# block_demux_pwm.net
KiCad netlist of a schematic drawn in EAGLE
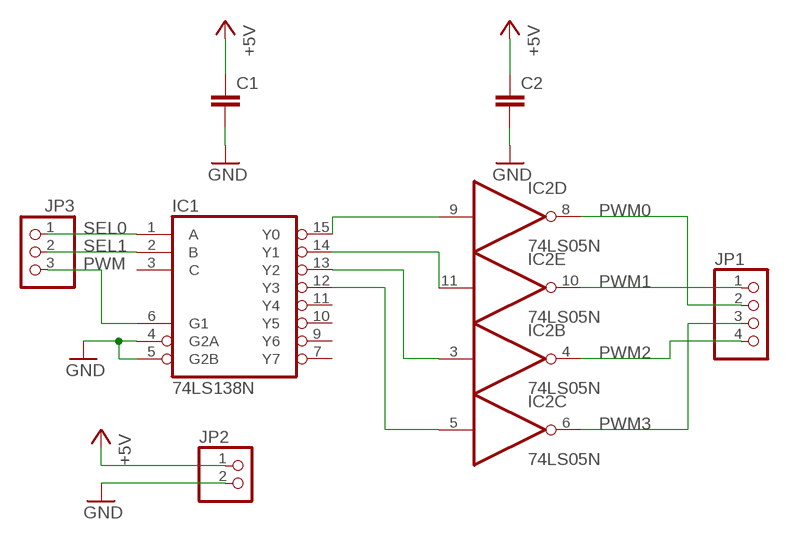
[diagram p0: schematic, sheet 1]

(export (version "E")
  (design (tool "Eeschema 10.0.6"))
  (components
    (comp (ref "C1")
      (value "C-EU050-025X075")
      (footprint "eagle-import:C050-025X075")
      (libsource (lib "eagle-import") (part "C-EU050-025X075"))
    )
    (comp (ref "C2")
      (value "C-EU050-025X075")
      (footprint "eagle-import:C050-025X075")
      (libsource (lib "eagle-import") (part "C-EU050-025X075"))
    )
    (comp (ref "IC1")
      (value "74LS138N")
      (footprint "eagle-import:DIL16")
      (libsource (lib "eagle-import") (part "74138NLS"))
    )
    (comp (ref "IC2")
      (value "74LS05N")
      (footprint "eagle-import:DIL14")
      (libsource (lib "eagle-import") (part "7405NLS"))
    )
    (comp (ref "JP1")
      (value "PINHD-1X4")
      (footprint "eagle-import:1X04")
      (libsource (lib "eagle-import") (part "PINHD-1X4"))
    )
    (comp (ref "JP2")
      (value "PINHD-1X2")
      (footprint "eagle-import:1X02")
      (libsource (lib "eagle-import") (part "PINHD-1X2"))
    )
    (comp (ref "JP3")
      (value "PINHD-1X3")
      (footprint "eagle-import:1X03")
      (libsource (lib "eagle-import") (part "PINHD-1X3"))
    )
  )
  (nets
    (net (code "1") (name "+5V") (class "Default")
      (node (ref "C1") (pin "1") (pinfunction "1_1") (pintype "passive"))
      (node (ref "C2") (pin "1") (pinfunction "1_1") (pintype "passive"))
      (node (ref "JP2") (pin "1") (pinfunction "1_1") (pintype "passive"))
    )
    (net (code "2") (name "/PWM") (class "Default")
      (node (ref "IC1") (pin "6") (pinfunction "G1_6") (pintype "input"))
      (node (ref "JP3") (pin "3") (pinfunction "3_3") (pintype "passive"))
    )
    (net (code "3") (name "/PWM0") (class "Default")
      (node (ref "IC2") (pin "8") (pinfunction "O_8") (pintype "open_collector"))
      (node (ref "JP1") (pin "2") (pinfunction "2_2") (pintype "passive"))
    )
    (net (code "4") (name "/PWM1") (class "Default")
      (node (ref "IC2") (pin "10") (pinfunction "O_10") (pintype "open_collector"))
      (node (ref "JP1") (pin "1") (pinfunction "1_1") (pintype "passive"))
    )
    (net (code "5") (name "/PWM2") (class "Default")
      (node (ref "IC2") (pin "4") (pinfunction "O_4") (pintype "open_collector"))
      (node (ref "JP1") (pin "4") (pinfunction "4_4") (pintype "passive"))
    )
    (net (code "6") (name "/PWM3") (class "Default")
      (node (ref "IC2") (pin "6") (pinfunction "O_6") (pintype "open_collector"))
      (node (ref "JP1") (pin "3") (pinfunction "3_3") (pintype "passive"))
    )
    (net (code "7") (name "/SEL0") (class "Default")
      (node (ref "IC1") (pin "1") (pinfunction "A_1") (pintype "input"))
      (node (ref "JP3") (pin "1") (pinfunction "1_1") (pintype "passive"))
    )
    (net (code "8") (name "/SEL1") (class "Default")
      (node (ref "IC1") (pin "2") (pinfunction "B_2") (pintype "input"))
      (node (ref "JP3") (pin "2") (pinfunction "2_2") (pintype "passive"))
    )
    (net (code "9") (name "GND") (class "Default")
      (node (ref "C1") (pin "2") (pinfunction "2_2") (pintype "passive"))
      (node (ref "C2") (pin "2") (pinfunction "2_2") (pintype "passive"))
      (node (ref "IC1") (pin "4") (pinfunction "G2A_4") (pintype "input"))
      (node (ref "IC1") (pin "5") (pinfunction "G2B_5") (pintype "input"))
      (node (ref "JP2") (pin "2") (pinfunction "2_2") (pintype "passive"))
    )
    (net (code "10") (name "Net-(IC1A-Y0)") (class "Default")
      (node (ref "IC1") (pin "15") (pinfunction "Y0_15") (pintype "output"))
      (node (ref "IC2") (pin "9") (pinfunction "I_9") (pintype "input"))
    )
    (net (code "11") (name "Net-(IC1A-Y1)") (class "Default")
      (node (ref "IC1") (pin "14") (pinfunction "Y1_14") (pintype "output"))
      (node (ref "IC2") (pin "11") (pinfunction "I_11") (pintype "input"))
    )
    (net (code "12") (name "Net-(IC1A-Y2)") (class "Default")
      (node (ref "IC1") (pin "13") (pinfunction "Y2_13") (pintype "output"))
      (node (ref "IC2") (pin "3") (pinfunction "I_3") (pintype "input"))
    )
    (net (code "13") (name "Net-(IC1A-Y3)") (class "Default")
      (node (ref "IC1") (pin "12") (pinfunction "Y3_12") (pintype "output"))
      (node (ref "IC2") (pin "5") (pinfunction "I_5") (pintype "input"))
    )
    (net (code "14") (name "unconnected-(IC1A-C-Pad3)") (class "Default")
      (node (ref "IC1") (pin "3") (pinfunction "C_3") (pintype "input"))
    )
    (net (code "15") (name "unconnected-(IC1A-Y4-Pad11)") (class "Default")
      (node (ref "IC1") (pin "11") (pinfunction "Y4_11") (pintype "output"))
    )
    (net (code "16") (name "unconnected-(IC1A-Y5-Pad10)") (class "Default")
      (node (ref "IC1") (pin "10") (pinfunction "Y5_10") (pintype "output"))
    )
    (net (code "17") (name "unconnected-(IC1A-Y6-Pad9)") (class "Default")
      (node (ref "IC1") (pin "9") (pinfunction "Y6_9") (pintype "output"))
    )
    (net (code "18") (name "unconnected-(IC1A-Y7-Pad7)") (class "Default")
      (node (ref "IC1") (pin "7") (pinfunction "Y7_7") (pintype "output"))
    )
  )
)
